# numpad_v1a.net
KiCad netlist of a schematic drawn in EAGLE
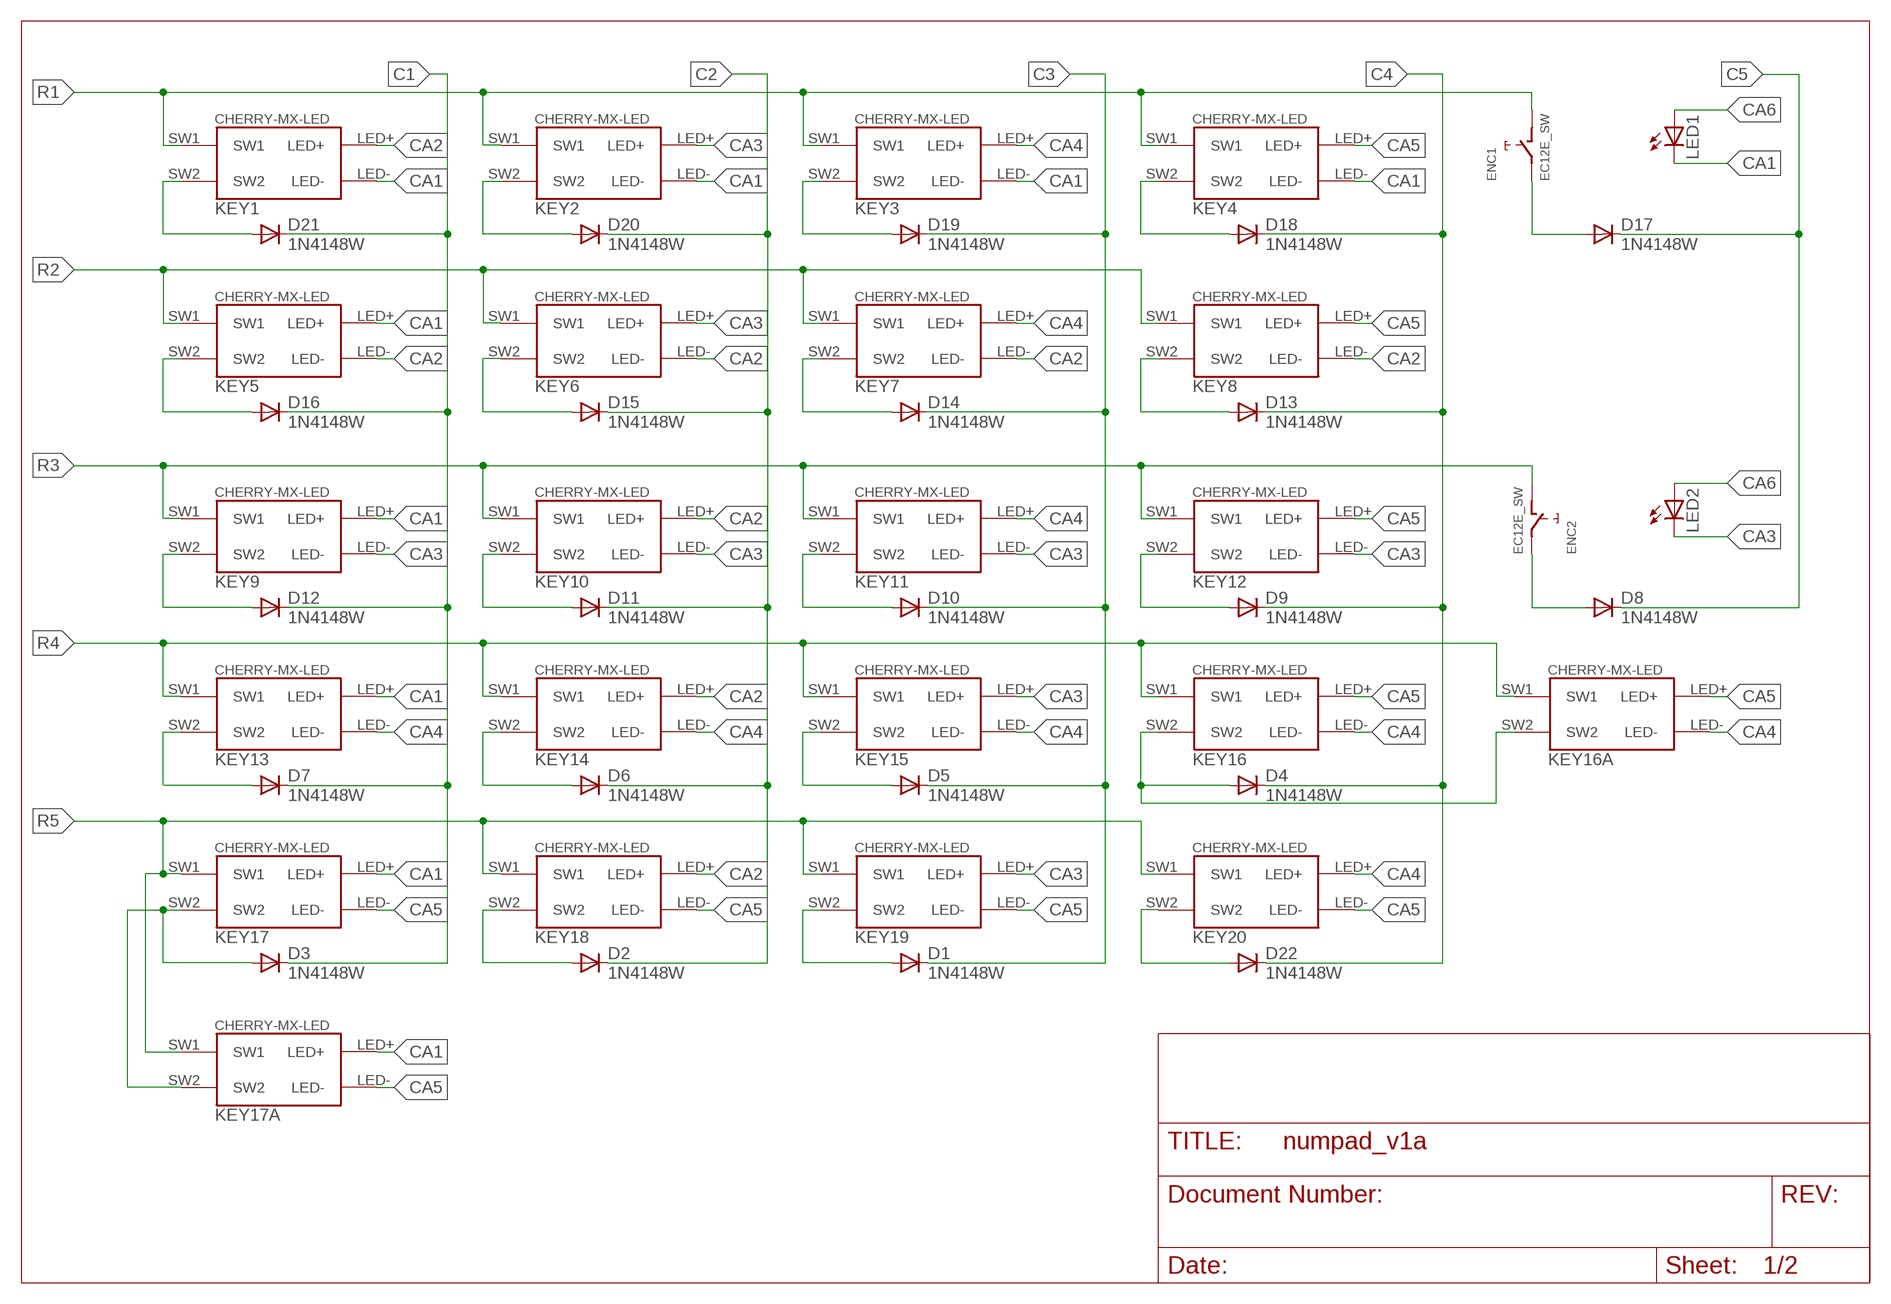
[diagram p0: schematic, sheet 1]
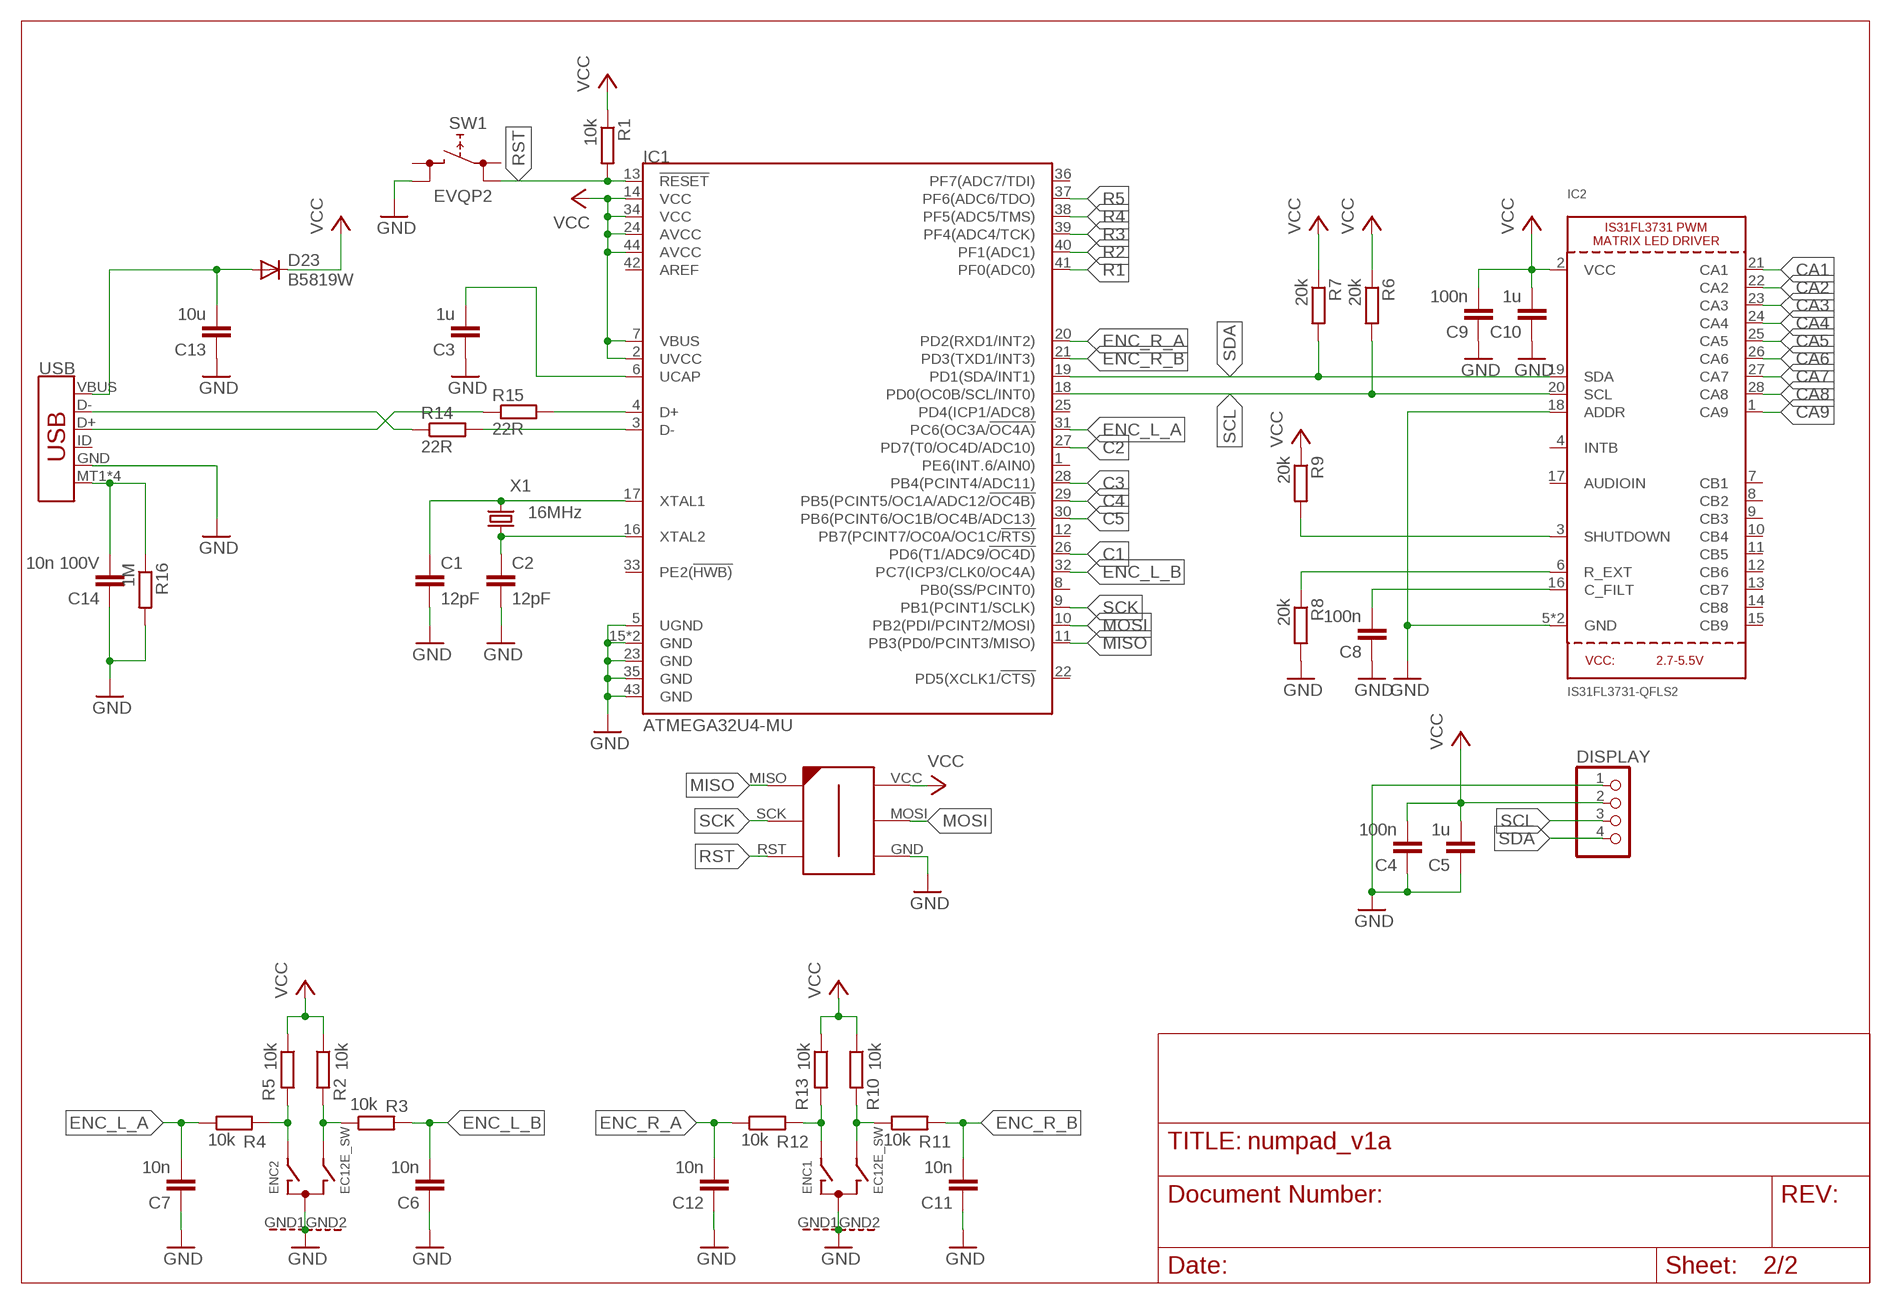
[diagram p1: schematic, sheet 2]

(export (version "E")
  (design (tool "Eeschema 10.0.6"))
  (components
    (comp (ref "D1")
      (value "1N4148W")
      (footprint "eagle-import:SOD123")
      (libsource (lib "eagle-import") (part "DIODE-SOD123"))
    )
    (comp (ref "D2")
      (value "1N4148W")
      (footprint "eagle-import:SOD123")
      (libsource (lib "eagle-import") (part "DIODE-SOD123"))
    )
    (comp (ref "D3")
      (value "1N4148W")
      (footprint "eagle-import:SOD123")
      (libsource (lib "eagle-import") (part "DIODE-SOD123"))
    )
    (comp (ref "D4")
      (value "1N4148W")
      (footprint "eagle-import:SOD123")
      (libsource (lib "eagle-import") (part "DIODE-SOD123"))
    )
    (comp (ref "D5")
      (value "1N4148W")
      (footprint "eagle-import:SOD123")
      (libsource (lib "eagle-import") (part "DIODE-SOD123"))
    )
    (comp (ref "D6")
      (value "1N4148W")
      (footprint "eagle-import:SOD123")
      (libsource (lib "eagle-import") (part "DIODE-SOD123"))
    )
    (comp (ref "D7")
      (value "1N4148W")
      (footprint "eagle-import:SOD123")
      (libsource (lib "eagle-import") (part "DIODE-SOD123"))
    )
    (comp (ref "D8")
      (value "1N4148W")
      (footprint "eagle-import:SOD123")
      (libsource (lib "eagle-import") (part "DIODE-SOD123"))
    )
    (comp (ref "D9")
      (value "1N4148W")
      (footprint "eagle-import:SOD123")
      (libsource (lib "eagle-import") (part "DIODE-SOD123"))
    )
    (comp (ref "D10")
      (value "1N4148W")
      (footprint "eagle-import:SOD123")
      (libsource (lib "eagle-import") (part "DIODE-SOD123"))
    )
    (comp (ref "D11")
      (value "1N4148W")
      (footprint "eagle-import:SOD123")
      (libsource (lib "eagle-import") (part "DIODE-SOD123"))
    )
    (comp (ref "D12")
      (value "1N4148W")
      (footprint "eagle-import:SOD123")
      (libsource (lib "eagle-import") (part "DIODE-SOD123"))
    )
    (comp (ref "D13")
      (value "1N4148W")
      (footprint "eagle-import:SOD123")
      (libsource (lib "eagle-import") (part "DIODE-SOD123"))
    )
    (comp (ref "D14")
      (value "1N4148W")
      (footprint "eagle-import:SOD123")
      (libsource (lib "eagle-import") (part "DIODE-SOD123"))
    )
    (comp (ref "D15")
      (value "1N4148W")
      (footprint "eagle-import:SOD123")
      (libsource (lib "eagle-import") (part "DIODE-SOD123"))
    )
    (comp (ref "D16")
      (value "1N4148W")
      (footprint "eagle-import:SOD123")
      (libsource (lib "eagle-import") (part "DIODE-SOD123"))
    )
    (comp (ref "D17")
      (value "1N4148W")
      (footprint "eagle-import:SOD123")
      (libsource (lib "eagle-import") (part "DIODE-SOD123"))
    )
    (comp (ref "D18")
      (value "1N4148W")
      (footprint "eagle-import:SOD123")
      (libsource (lib "eagle-import") (part "DIODE-SOD123"))
    )
    (comp (ref "D19")
      (value "1N4148W")
      (footprint "eagle-import:SOD123")
      (libsource (lib "eagle-import") (part "DIODE-SOD123"))
    )
    (comp (ref "D20")
      (value "1N4148W")
      (footprint "eagle-import:SOD123")
      (libsource (lib "eagle-import") (part "DIODE-SOD123"))
    )
    (comp (ref "D21")
      (value "1N4148W")
      (footprint "eagle-import:SOD123")
      (libsource (lib "eagle-import") (part "DIODE-SOD123"))
    )
    (comp (ref "D22")
      (value "1N4148W")
      (footprint "eagle-import:SOD123")
      (libsource (lib "eagle-import") (part "DIODE-SOD123"))
    )
    (comp (ref "ENC1")
      (value "EC12E_SW")
      (footprint "eagle-import:ALPS_EC12E_SW")
      (fields (field (name "MPN") "EC12E2424407"))
      (libsource (lib "eagle-import") (part "EC12E_SW"))
    )
    (comp (ref "ENC2")
      (value "EC12E_SW")
      (footprint "eagle-import:ALPS_EC12E_SW")
      (fields (field (name "MPN") "EC12E2424407"))
      (libsource (lib "eagle-import") (part "EC12E_SW"))
    )
    (comp (ref "KEY1")
      (value "CHERRY-MX-LED")
      (footprint "eagle-import:CHERRY-MX-LED")
      (libsource (lib "eagle-import") (part "CHERRY-MX-LED"))
    )
    (comp (ref "KEY2")
      (value "CHERRY-MX-LED")
      (footprint "eagle-import:CHERRY-MX-LED")
      (libsource (lib "eagle-import") (part "CHERRY-MX-LED"))
    )
    (comp (ref "KEY3")
      (value "CHERRY-MX-LED")
      (footprint "eagle-import:CHERRY-MX-LED")
      (libsource (lib "eagle-import") (part "CHERRY-MX-LED"))
    )
    (comp (ref "KEY4")
      (value "CHERRY-MX-LED")
      (footprint "eagle-import:CHERRY-MX-LED")
      (libsource (lib "eagle-import") (part "CHERRY-MX-LED"))
    )
    (comp (ref "KEY5")
      (value "CHERRY-MX-LED")
      (footprint "eagle-import:CHERRY-MX-LED")
      (libsource (lib "eagle-import") (part "CHERRY-MX-LED"))
    )
    (comp (ref "KEY6")
      (value "CHERRY-MX-LED")
      (footprint "eagle-import:CHERRY-MX-LED")
      (libsource (lib "eagle-import") (part "CHERRY-MX-LED"))
    )
    (comp (ref "KEY7")
      (value "CHERRY-MX-LED")
      (footprint "eagle-import:CHERRY-MX-LED")
      (libsource (lib "eagle-import") (part "CHERRY-MX-LED"))
    )
    (comp (ref "KEY8")
      (value "CHERRY-MX-LED")
      (footprint "eagle-import:CHERRY-MX-LED")
      (libsource (lib "eagle-import") (part "CHERRY-MX-LED"))
    )
    (comp (ref "KEY9")
      (value "CHERRY-MX-LED")
      (footprint "eagle-import:CHERRY-MX-LED")
      (libsource (lib "eagle-import") (part "CHERRY-MX-LED"))
    )
    (comp (ref "KEY10")
      (value "CHERRY-MX-LED")
      (footprint "eagle-import:CHERRY-MX-LED")
      (libsource (lib "eagle-import") (part "CHERRY-MX-LED"))
    )
    (comp (ref "KEY11")
      (value "CHERRY-MX-LED")
      (footprint "eagle-import:CHERRY-MX-LED")
      (libsource (lib "eagle-import") (part "CHERRY-MX-LED"))
    )
    (comp (ref "KEY12")
      (value "CHERRY-MX-LED")
      (footprint "eagle-import:CHERRY-MX-LED")
      (libsource (lib "eagle-import") (part "CHERRY-MX-LED"))
    )
    (comp (ref "KEY13")
      (value "CHERRY-MX-LED")
      (footprint "eagle-import:CHERRY-MX-LED")
      (libsource (lib "eagle-import") (part "CHERRY-MX-LED"))
    )
    (comp (ref "KEY14")
      (value "CHERRY-MX-LED")
      (footprint "eagle-import:CHERRY-MX-LED")
      (libsource (lib "eagle-import") (part "CHERRY-MX-LED"))
    )
    (comp (ref "KEY15")
      (value "CHERRY-MX-LED")
      (footprint "eagle-import:CHERRY-MX-LED")
      (libsource (lib "eagle-import") (part "CHERRY-MX-LED"))
    )
    (comp (ref "KEY16")
      (value "CHERRY-MX-LED_NOHOLES")
      (footprint "eagle-import:CHERRY-MX-LED_NOHOLES")
      (libsource (lib "eagle-import") (part "CHERRY-MX-LED_NOHOLES"))
    )
    (comp (ref "KEY16A")
      (value "CHERRY-MX-LED")
      (footprint "eagle-import:CHERRY-MX-LED")
      (libsource (lib "eagle-import") (part "CHERRY-MX-LED"))
    )
    (comp (ref "KEY17")
      (value "CHERRY-MX-LED")
      (footprint "eagle-import:CHERRY-MX-LED")
      (libsource (lib "eagle-import") (part "CHERRY-MX-LED"))
    )
    (comp (ref "KEY17A")
      (value "CHERRY-MX-LED_NOHOLES")
      (footprint "eagle-import:CHERRY-MX-LED_NOHOLES")
      (libsource (lib "eagle-import") (part "CHERRY-MX-LED_NOHOLES"))
    )
    (comp (ref "KEY18")
      (value "CHERRY-MX-LED")
      (footprint "eagle-import:CHERRY-MX-LED")
      (libsource (lib "eagle-import") (part "CHERRY-MX-LED"))
    )
    (comp (ref "KEY19")
      (value "CHERRY-MX-LED")
      (footprint "eagle-import:CHERRY-MX-LED")
      (libsource (lib "eagle-import") (part "CHERRY-MX-LED"))
    )
    (comp (ref "KEY20")
      (value "CHERRY-MX-LED")
      (footprint "eagle-import:CHERRY-MX-LED")
      (libsource (lib "eagle-import") (part "CHERRY-MX-LED"))
    )
    (comp (ref "LED1")
      (value "LED3MM")
      (footprint "eagle-import:LED3MM")
      (libsource (lib "eagle-import") (part "LED3MM"))
    )
    (comp (ref "LED2")
      (value "LED3MM")
      (footprint "eagle-import:LED3MM")
      (libsource (lib "eagle-import") (part "LED3MM"))
    )
    (comp (ref "C1")
      (value "12pF")
      (footprint "eagle-import:C0603")
      (libsource (lib "eagle-import") (part "C-EUC0603"))
    )
    (comp (ref "C2")
      (value "12pF")
      (footprint "eagle-import:C0603")
      (libsource (lib "eagle-import") (part "C-EUC0603"))
    )
    (comp (ref "C3")
      (value "1u")
      (footprint "eagle-import:C0603")
      (libsource (lib "eagle-import") (part "C-EUC0603"))
    )
    (comp (ref "C4")
      (value "100n")
      (footprint "eagle-import:C0603")
      (libsource (lib "eagle-import") (part "C-EUC0603"))
    )
    (comp (ref "C5")
      (value "1u")
      (footprint "eagle-import:C0603")
      (libsource (lib "eagle-import") (part "C-EUC0603"))
    )
    (comp (ref "C6")
      (value "10n")
      (footprint "eagle-import:C0603")
      (libsource (lib "eagle-import") (part "C-EUC0603"))
    )
    (comp (ref "C7")
      (value "10n")
      (footprint "eagle-import:C0603")
      (libsource (lib "eagle-import") (part "C-EUC0603"))
    )
    (comp (ref "C8")
      (value "100n")
      (footprint "eagle-import:C0603")
      (libsource (lib "eagle-import") (part "C-EUC0603"))
    )
    (comp (ref "C9")
      (value "100n")
      (footprint "eagle-import:C0603")
      (libsource (lib "eagle-import") (part "C-EUC0603"))
    )
    (comp (ref "C10")
      (value "1u")
      (footprint "eagle-import:C0603")
      (libsource (lib "eagle-import") (part "C-EUC0603"))
    )
    (comp (ref "C11")
      (value "10n")
      (footprint "eagle-import:C0603")
      (libsource (lib "eagle-import") (part "C-EUC0603"))
    )
    (comp (ref "C12")
      (value "10n")
      (footprint "eagle-import:C0603")
      (libsource (lib "eagle-import") (part "C-EUC0603"))
    )
    (comp (ref "C13")
      (value "10u")
      (footprint "eagle-import:C0603")
      (libsource (lib "eagle-import") (part "C-EUC0603"))
    )
    (comp (ref "C14")
      (value "10n 100V")
      (footprint "eagle-import:C0603")
      (libsource (lib "eagle-import") (part "C-EUC0603"))
    )
    (comp (ref "D23")
      (value "B5819W")
      (footprint "eagle-import:SOD123")
      (libsource (lib "eagle-import") (part "DIODE-SOD123"))
    )
    (comp (ref "DISPLAY")
      (value "PINHD-1X4")
      (footprint "eagle-import:1X04")
      (libsource (lib "eagle-import") (part "PINHD-1X4"))
    )
    (comp (ref "IC1")
      (value "ATMEGA32U4-MU")
      (footprint "eagle-import:QFN44G-0.5-7X7MM")
      (fields (field (name "MF") "Microchip") (field (name "MP") "ATMEGA32U4-MUR"))
      (libsource (lib "eagle-import") (part "MCU-ATMEGA32U4-MUR(VQFN44)"))
    )
    (comp (ref "IC2")
      (value "IS31FL3731-QFLS2")
      (footprint "eagle-import:QFN28_4MM_0.4MM")
      (libsource (lib "eagle-import") (part "IS31FL3731QFN"))
    )
    (comp (ref "ISP")
      (value "AVR-ISP-6-EDGE")
      (footprint "eagle-import:6PAD_ISP")
      (libsource (lib "eagle-import") (part "AVR-ISP-6-EDGE"))
    )
    (comp (ref "R1")
      (value "10k")
      (footprint "eagle-import:R0603")
      (libsource (lib "eagle-import") (part "R-EU_R0603"))
    )
    (comp (ref "R2")
      (value "10k")
      (footprint "eagle-import:R0603")
      (libsource (lib "eagle-import") (part "R-EU_R0603"))
    )
    (comp (ref "R3")
      (value "10k")
      (footprint "eagle-import:R0603")
      (libsource (lib "eagle-import") (part "R-EU_R0603"))
    )
    (comp (ref "R4")
      (value "10k")
      (footprint "eagle-import:R0603")
      (libsource (lib "eagle-import") (part "R-EU_R0603"))
    )
    (comp (ref "R5")
      (value "10k")
      (footprint "eagle-import:R0603")
      (libsource (lib "eagle-import") (part "R-EU_R0603"))
    )
    (comp (ref "R6")
      (value "20k")
      (footprint "eagle-import:R0603")
      (libsource (lib "eagle-import") (part "R-EU_R0603"))
    )
    (comp (ref "R7")
      (value "20k")
      (footprint "eagle-import:R0603")
      (libsource (lib "eagle-import") (part "R-EU_R0603"))
    )
    (comp (ref "R8")
      (value "20k")
      (footprint "eagle-import:R0603")
      (libsource (lib "eagle-import") (part "R-EU_R0603"))
    )
    (comp (ref "R9")
      (value "20k")
      (footprint "eagle-import:R0603")
      (libsource (lib "eagle-import") (part "R-EU_R0603"))
    )
    (comp (ref "R10")
      (value "10k")
      (footprint "eagle-import:R0603")
      (libsource (lib "eagle-import") (part "R-EU_R0603"))
    )
    (comp (ref "R11")
      (value "10k")
      (footprint "eagle-import:R0603")
      (libsource (lib "eagle-import") (part "R-EU_R0603"))
    )
    (comp (ref "R12")
      (value "10k")
      (footprint "eagle-import:R0603")
      (libsource (lib "eagle-import") (part "R-EU_R0603"))
    )
    (comp (ref "R13")
      (value "10k")
      (footprint "eagle-import:R0603")
      (libsource (lib "eagle-import") (part "R-EU_R0603"))
    )
    (comp (ref "R14")
      (value "22R")
      (footprint "eagle-import:R0603")
      (libsource (lib "eagle-import") (part "R-EU_R0603"))
    )
    (comp (ref "R15")
      (value "22R")
      (footprint "eagle-import:R0603")
      (libsource (lib "eagle-import") (part "R-EU_R0603"))
    )
    (comp (ref "R16")
      (value "1M")
      (footprint "eagle-import:R0603")
      (libsource (lib "eagle-import") (part "R-EU_R0603"))
    )
    (comp (ref "SW1")
      (value "EVQP2")
      (footprint "eagle-import:EVQP2")
      (libsource (lib "eagle-import") (part "EVQP2"))
    )
    (comp (ref "USB")
      (value "USB_MICRO-B_SMT")
      (footprint "eagle-import:USB-MICROB")
      (libsource (lib "eagle-import") (part "USB_MICRO-B_SMT"))
    )
    (comp (ref "X1")
      (value "16MHz")
      (footprint "eagle-import:3.2X2.5_KX-7")
      (libsource (lib "eagle-import") (part "KX-7"))
    )
  )
  (nets
    (net (code "1") (name "C1") (class "Default")
      (node (ref "D12") (pin "C") (pinfunction "C_C") (pintype "passive"))
      (node (ref "D16") (pin "C") (pinfunction "C_C") (pintype "passive"))
      (node (ref "D21") (pin "C") (pinfunction "C_C") (pintype "passive"))
      (node (ref "D3") (pin "C") (pinfunction "C_C") (pintype "passive"))
      (node (ref "D7") (pin "C") (pinfunction "C_C") (pintype "passive"))
      (node (ref "IC1") (pin "26") (pinfunction "PD6(T1/ADC9/~{OC4D})_26") (pintype "bidirectional"))
    )
    (net (code "2") (name "C2") (class "Default")
      (node (ref "D11") (pin "C") (pinfunction "C_C") (pintype "passive"))
      (node (ref "D15") (pin "C") (pinfunction "C_C") (pintype "passive"))
      (node (ref "D2") (pin "C") (pinfunction "C_C") (pintype "passive"))
      (node (ref "D20") (pin "C") (pinfunction "C_C") (pintype "passive"))
      (node (ref "D6") (pin "C") (pinfunction "C_C") (pintype "passive"))
      (node (ref "IC1") (pin "27") (pinfunction "PD7(T0/OC4D/ADC10)_27") (pintype "bidirectional"))
    )
    (net (code "3") (name "C3") (class "Default")
      (node (ref "D1") (pin "C") (pinfunction "C_C") (pintype "passive"))
      (node (ref "D10") (pin "C") (pinfunction "C_C") (pintype "passive"))
      (node (ref "D14") (pin "C") (pinfunction "C_C") (pintype "passive"))
      (node (ref "D19") (pin "C") (pinfunction "C_C") (pintype "passive"))
      (node (ref "D5") (pin "C") (pinfunction "C_C") (pintype "passive"))
      (node (ref "IC1") (pin "28") (pinfunction "PB4(PCINT4/ADC11)_28") (pintype "bidirectional"))
    )
    (net (code "4") (name "C4") (class "Default")
      (node (ref "D13") (pin "C") (pinfunction "C_C") (pintype "passive"))
      (node (ref "D18") (pin "C") (pinfunction "C_C") (pintype "passive"))
      (node (ref "D22") (pin "C") (pinfunction "C_C") (pintype "passive"))
      (node (ref "D4") (pin "C") (pinfunction "C_C") (pintype "passive"))
      (node (ref "D9") (pin "C") (pinfunction "C_C") (pintype "passive"))
      (node (ref "IC1") (pin "29") (pinfunction "PB5(PCINT5/OC1A/ADC12/~{OC4B})_29") (pintype "bidirectional"))
    )
    (net (code "5") (name "C5") (class "Default")
      (node (ref "D17") (pin "C") (pinfunction "C_C") (pintype "passive"))
      (node (ref "D8") (pin "C") (pinfunction "C_C") (pintype "passive"))
      (node (ref "IC1") (pin "30") (pinfunction "PB6(PCINT6/OC1B/OC4B/ADC13)_30") (pintype "bidirectional"))
    )
    (net (code "6") (name "CA1") (class "Default")
      (node (ref "IC2") (pin "21") (pinfunction "CA1_21") (pintype "bidirectional"))
      (node (ref "KEY1") (pin "LED-") (pinfunction "LED-_LED-") (pintype "bidirectional"))
      (node (ref "KEY13") (pin "LED+") (pinfunction "LED+_LED+") (pintype "bidirectional"))
      (node (ref "KEY17") (pin "LED+") (pinfunction "LED+_LED+") (pintype "bidirectional"))
      (node (ref "KEY17A") (pin "LED+") (pinfunction "LED+_LED+") (pintype "bidirectional"))
      (node (ref "KEY2") (pin "LED-") (pinfunction "LED-_LED-") (pintype "bidirectional"))
      (node (ref "KEY3") (pin "LED-") (pinfunction "LED-_LED-") (pintype "bidirectional"))
      (node (ref "KEY4") (pin "LED-") (pinfunction "LED-_LED-") (pintype "bidirectional"))
      (node (ref "KEY5") (pin "LED+") (pinfunction "LED+_LED+") (pintype "bidirectional"))
      (node (ref "KEY9") (pin "LED+") (pinfunction "LED+_LED+") (pintype "bidirectional"))
      (node (ref "LED1") (pin "K") (pinfunction "C_K") (pintype "passive"))
    )
    (net (code "7") (name "CA2") (class "Default")
      (node (ref "IC2") (pin "22") (pinfunction "CA2_22") (pintype "bidirectional"))
      (node (ref "KEY1") (pin "LED+") (pinfunction "LED+_LED+") (pintype "bidirectional"))
      (node (ref "KEY10") (pin "LED+") (pinfunction "LED+_LED+") (pintype "bidirectional"))
      (node (ref "KEY14") (pin "LED+") (pinfunction "LED+_LED+") (pintype "bidirectional"))
      (node (ref "KEY18") (pin "LED+") (pinfunction "LED+_LED+") (pintype "bidirectional"))
      (node (ref "KEY5") (pin "LED-") (pinfunction "LED-_LED-") (pintype "bidirectional"))
      (node (ref "KEY6") (pin "LED-") (pinfunction "LED-_LED-") (pintype "bidirectional"))
      (node (ref "KEY7") (pin "LED-") (pinfunction "LED-_LED-") (pintype "bidirectional"))
      (node (ref "KEY8") (pin "LED-") (pinfunction "LED-_LED-") (pintype "bidirectional"))
    )
    (net (code "8") (name "CA3") (class "Default")
      (node (ref "IC2") (pin "23") (pinfunction "CA3_23") (pintype "bidirectional"))
      (node (ref "KEY10") (pin "LED-") (pinfunction "LED-_LED-") (pintype "bidirectional"))
      (node (ref "KEY11") (pin "LED-") (pinfunction "LED-_LED-") (pintype "bidirectional"))
      (node (ref "KEY12") (pin "LED-") (pinfunction "LED-_LED-") (pintype "bidirectional"))
      (node (ref "KEY15") (pin "LED+") (pinfunction "LED+_LED+") (pintype "bidirectional"))
      (node (ref "KEY19") (pin "LED+") (pinfunction "LED+_LED+") (pintype "bidirectional"))
      (node (ref "KEY2") (pin "LED+") (pinfunction "LED+_LED+") (pintype "bidirectional"))
      (node (ref "KEY6") (pin "LED+") (pinfunction "LED+_LED+") (pintype "bidirectional"))
      (node (ref "KEY9") (pin "LED-") (pinfunction "LED-_LED-") (pintype "bidirectional"))
      (node (ref "LED2") (pin "K") (pinfunction "C_K") (pintype "passive"))
    )
    (net (code "9") (name "CA4") (class "Default")
      (node (ref "IC2") (pin "24") (pinfunction "CA4_24") (pintype "bidirectional"))
      (node (ref "KEY11") (pin "LED+") (pinfunction "LED+_LED+") (pintype "bidirectional"))
      (node (ref "KEY13") (pin "LED-") (pinfunction "LED-_LED-") (pintype "bidirectional"))
      (node (ref "KEY14") (pin "LED-") (pinfunction "LED-_LED-") (pintype "bidirectional"))
      (node (ref "KEY15") (pin "LED-") (pinfunction "LED-_LED-") (pintype "bidirectional"))
      (node (ref "KEY16") (pin "LED-") (pinfunction "LED-_LED-") (pintype "bidirectional"))
      (node (ref "KEY16A") (pin "LED-") (pinfunction "LED-_LED-") (pintype "bidirectional"))
      (node (ref "KEY20") (pin "LED+") (pinfunction "LED+_LED+") (pintype "bidirectional"))
      (node (ref "KEY3") (pin "LED+") (pinfunction "LED+_LED+") (pintype "bidirectional"))
      (node (ref "KEY7") (pin "LED+") (pinfunction "LED+_LED+") (pintype "bidirectional"))
    )
    (net (code "10") (name "CA5") (class "Default")
      (node (ref "IC2") (pin "25") (pinfunction "CA5_25") (pintype "bidirectional"))
      (node (ref "KEY12") (pin "LED+") (pinfunction "LED+_LED+") (pintype "bidirectional"))
      (node (ref "KEY16") (pin "LED+") (pinfunction "LED+_LED+") (pintype "bidirectional"))
      (node (ref "KEY16A") (pin "LED+") (pinfunction "LED+_LED+") (pintype "bidirectional"))
      (node (ref "KEY17") (pin "LED-") (pinfunction "LED-_LED-") (pintype "bidirectional"))
      (node (ref "KEY17A") (pin "LED-") (pinfunction "LED-_LED-") (pintype "bidirectional"))
      (node (ref "KEY18") (pin "LED-") (pinfunction "LED-_LED-") (pintype "bidirectional"))
      (node (ref "KEY19") (pin "LED-") (pinfunction "LED-_LED-") (pintype "bidirectional"))
      (node (ref "KEY20") (pin "LED-") (pinfunction "LED-_LED-") (pintype "bidirectional"))
      (node (ref "KEY4") (pin "LED+") (pinfunction "LED+_LED+") (pintype "bidirectional"))
      (node (ref "KEY8") (pin "LED+") (pinfunction "LED+_LED+") (pintype "bidirectional"))
    )
    (net (code "11") (name "CA6") (class "Default")
      (node (ref "IC2") (pin "26") (pinfunction "CA6_26") (pintype "bidirectional"))
      (node (ref "LED1") (pin "A") (pinfunction "A_A") (pintype "passive"))
      (node (ref "LED2") (pin "A") (pinfunction "A_A") (pintype "passive"))
    )
    (net (code "12") (name "CA7") (class "Default")
      (node (ref "IC2") (pin "27") (pinfunction "CA7_27") (pintype "bidirectional"))
    )
    (net (code "13") (name "CA8") (class "Default")
      (node (ref "IC2") (pin "28") (pinfunction "CA8_28") (pintype "bidirectional"))
    )
    (net (code "14") (name "CA9") (class "Default")
      (node (ref "IC2") (pin "1") (pinfunction "CA9_1") (pintype "bidirectional"))
    )
    (net (code "15") (name "ENC_L_A") (class "Default")
      (node (ref "C7") (pin "2") (pinfunction "2_2") (pintype "passive"))
      (node (ref "IC1") (pin "31") (pinfunction "PC6(OC3A/~{OC4A})_31") (pintype "bidirectional"))
      (node (ref "R4") (pin "1") (pinfunction "1_1") (pintype "passive"))
    )
    (net (code "16") (name "ENC_L_B") (class "Default")
      (node (ref "C6") (pin "2") (pinfunction "2_2") (pintype "passive"))
      (node (ref "IC1") (pin "32") (pinfunction "PC7(ICP3/CLK0/OC4A)_32") (pintype "bidirectional"))
      (node (ref "R3") (pin "2") (pinfunction "2_2") (pintype "passive"))
    )
    (net (code "17") (name "ENC_R_A") (class "Default")
      (node (ref "C12") (pin "2") (pinfunction "2_2") (pintype "passive"))
      (node (ref "IC1") (pin "20") (pinfunction "PD2(RXD1/INT2)_20") (pintype "bidirectional"))
      (node (ref "R12") (pin "1") (pinfunction "1_1") (pintype "passive"))
    )
    (net (code "18") (name "ENC_R_B") (class "Default")
      (node (ref "C11") (pin "2") (pinfunction "2_2") (pintype "passive"))
      (node (ref "IC1") (pin "21") (pinfunction "PD3(TXD1/INT3)_21") (pintype "bidirectional"))
      (node (ref "R11") (pin "2") (pinfunction "2_2") (pintype "passive"))
    )
    (net (code "19") (name "GND") (class "Default")
      (node (ref "C1") (pin "2") (pinfunction "2_2") (pintype "passive"))
      (node (ref "C10") (pin "1") (pinfunction "1_1") (pintype "passive"))
      (node (ref "C11") (pin "1") (pinfunction "1_1") (pintype "passive"))
      (node (ref "C12") (pin "1") (pinfunction "1_1") (pintype "passive"))
      (node (ref "C13") (pin "1") (pinfunction "1_1") (pintype "passive"))
      (node (ref "C14") (pin "1") (pinfunction "1_1") (pintype "passive"))
      (node (ref "C2") (pin "2") (pinfunction "2_2") (pintype "passive"))
      (node (ref "C3") (pin "1") (pinfunction "1_1") (pintype "passive"))
      (node (ref "C4") (pin "1") (pinfunction "1_1") (pintype "passive"))
      (node (ref "C5") (pin "1") (pinfunction "1_1") (pintype "passive"))
      (node (ref "C6") (pin "1") (pinfunction "1_1") (pintype "passive"))
      (node (ref "C7") (pin "1") (pinfunction "1_1") (pintype "passive"))
      (node (ref "C8") (pin "1") (pinfunction "1_1") (pintype "passive"))
      (node (ref "C9") (pin "1") (pinfunction "1_1") (pintype "passive"))
      (node (ref "DISPLAY") (pin "1") (pinfunction "1_1") (pintype "passive"))
      (node (ref "ENC1") (pin "C") (pinfunction "C_C") (pintype "passive"))
      (node (ref "ENC1") (pin "GND1") (pinfunction "G_GND1") (pintype "passive"))
      (node (ref "ENC1") (pin "GND2") (pinfunction "G_GND2") (pintype "passive"))
      (node (ref "ENC2") (pin "C") (pinfunction "C_C") (pintype "passive"))
      (node (ref "ENC2") (pin "GND1") (pinfunction "G_GND1") (pintype "passive"))
      (node (ref "ENC2") (pin "GND2") (pinfunction "G_GND2") (pintype "passive"))
      (node (ref "IC1") (pin "15") (pinfunction "GND_15") (pintype "bidirectional"))
      (node (ref "IC1") (pin "23") (pinfunction "GND_23") (pintype "bidirectional"))
      (node (ref "IC1") (pin "35") (pinfunction "GND_35") (pintype "bidirectional"))
      (node (ref "IC1") (pin "43") (pinfunction "GND_43") (pintype "bidirectional"))
      (node (ref "IC1") (pin "5") (pinfunction "UGND_5") (pintype "bidirectional"))
      (node (ref "IC1") (pin "TAB") (pinfunction "GND_TAB") (pintype "bidirectional"))
      (node (ref "IC2") (pin "18") (pinfunction "ADDR_18") (pintype "bidirectional"))
      (node (ref "IC2") (pin "5") (pinfunction "GND_5") (pintype "power_in"))
      (node (ref "IC2") (pin "THERMAL") (pinfunction "GND_THERMAL") (pintype "power_in"))
      (node (ref "ISP") (pin "GND") (pinfunction "P$4_GND") (pintype "bidirectional"))
      (node (ref "R16") (pin "2") (pinfunction "2_2") (pintype "passive"))
      (node (ref "R8") (pin "2") (pinfunction "2_2") (pintype "passive"))
      (node (ref "SW1") (pin "2") (pinfunction "1_2") (pintype "passive"))
      (node (ref "USB") (pin "GND") (pinfunction "GND_GND") (pintype "power_in"))
    )
    (net (code "20") (name "MISO") (class "Default")
      (node (ref "IC1") (pin "11") (pinfunction "PB3(PD0/PCINT3/MISO)_11") (pintype "bidirectional"))
      (node (ref "ISP") (pin "MISO") (pinfunction "P$1_MISO") (pintype "bidirectional"))
    )
    (net (code "21") (name "MOSI") (class "Default")
      (node (ref "IC1") (pin "10") (pinfunction "PB2(PDI/PCINT2/MOSI)_10") (pintype "bidirectional"))
      (node (ref "ISP") (pin "MOSI") (pinfunction "P$5_MOSI") (pintype "bidirectional"))
    )
    (net (code "22") (name "Net-(C13-Pad2)") (class "Default")
      (node (ref "C13") (pin "2") (pinfunction "2_2") (pintype "passive"))
      (node (ref "D23") (pin "A") (pinfunction "A_A") (pintype "passive"))
      (node (ref "USB") (pin "VBUS") (pinfunction "VBUS_VBUS") (pintype "power_in"))
    )
    (net (code "23") (name "Net-(C14-Pad2)") (class "Default")
      (node (ref "C14") (pin "2") (pinfunction "2_2") (pintype "passive"))
      (node (ref "R16") (pin "1") (pinfunction "1_1") (pintype "passive"))
      (node (ref "USB") (pin "MT1") (pinfunction "SHIELD_MT1") (pintype "bidirectional"))
      (node (ref "USB") (pin "MT2") (pinfunction "SHIELD_MT2") (pintype "bidirectional"))
      (node (ref "USB") (pin "P$1") (pinfunction "SHIELD_P$1") (pintype "bidirectional"))
      (node (ref "USB") (pin "P$2") (pinfunction "SHIELD_P$2") (pintype "bidirectional"))
    )
    (net (code "24") (name "Net-(D1-PadA)") (class "Default")
      (node (ref "D1") (pin "A") (pinfunction "A_A") (pintype "passive"))
      (node (ref "KEY19") (pin "SW2") (pinfunction "SW2_SW2") (pintype "bidirectional"))
    )
    (net (code "25") (name "Net-(D2-PadA)") (class "Default")
      (node (ref "D2") (pin "A") (pinfunction "A_A") (pintype "passive"))
      (node (ref "KEY18") (pin "SW2") (pinfunction "SW2_SW2") (pintype "bidirectional"))
    )
    (net (code "26") (name "Net-(D3-PadA)") (class "Default")
      (node (ref "D3") (pin "A") (pinfunction "A_A") (pintype "passive"))
      (node (ref "KEY17") (pin "SW2") (pinfunction "SW2_SW2") (pintype "bidirectional"))
      (node (ref "KEY17A") (pin "SW2") (pinfunction "SW2_SW2") (pintype "bidirectional"))
    )
    (net (code "27") (name "Net-(D4-PadA)") (class "Default")
      (node (ref "D4") (pin "A") (pinfunction "A_A") (pintype "passive"))
      (node (ref "KEY16") (pin "SW2") (pinfunction "SW2_SW2") (pintype "bidirectional"))
      (node (ref "KEY16A") (pin "SW2") (pinfunction "SW2_SW2") (pintype "bidirectional"))
    )
    (net (code "28") (name "Net-(D5-PadA)") (class "Default")
      (node (ref "D5") (pin "A") (pinfunction "A_A") (pintype "passive"))
      (node (ref "KEY15") (pin "SW2") (pinfunction "SW2_SW2") (pintype "bidirectional"))
    )
    (net (code "29") (name "Net-(D6-PadA)") (class "Default")
      (node (ref "D6") (pin "A") (pinfunction "A_A") (pintype "passive"))
      (node (ref "KEY14") (pin "SW2") (pinfunction "SW2_SW2") (pintype "bidirectional"))
    )
    (net (code "30") (name "Net-(D7-PadA)") (class "Default")
      (node (ref "D7") (pin "A") (pinfunction "A_A") (pintype "passive"))
      (node (ref "KEY13") (pin "SW2") (pinfunction "SW2_SW2") (pintype "bidirectional"))
    )
    (net (code "31") (name "Net-(D9-PadA)") (class "Default")
      (node (ref "D9") (pin "A") (pinfunction "A_A") (pintype "passive"))
      (node (ref "KEY12") (pin "SW2") (pinfunction "SW2_SW2") (pintype "bidirectional"))
    )
    (net (code "32") (name "Net-(D10-PadA)") (class "Default")
      (node (ref "D10") (pin "A") (pinfunction "A_A") (pintype "passive"))
      (node (ref "KEY11") (pin "SW2") (pinfunction "SW2_SW2") (pintype "bidirectional"))
    )
    (net (code "33") (name "Net-(D11-PadA)") (class "Default")
      (node (ref "D11") (pin "A") (pinfunction "A_A") (pintype "passive"))
      (node (ref "KEY10") (pin "SW2") (pinfunction "SW2_SW2") (pintype "bidirectional"))
    )
    (net (code "34") (name "Net-(D12-PadA)") (class "Default")
      (node (ref "D12") (pin "A") (pinfunction "A_A") (pintype "passive"))
      (node (ref "KEY9") (pin "SW2") (pinfunction "SW2_SW2") (pintype "bidirectional"))
    )
    (net (code "35") (name "Net-(D13-PadA)") (class "Default")
      (node (ref "D13") (pin "A") (pinfunction "A_A") (pintype "passive"))
      (node (ref "KEY8") (pin "SW2") (pinfunction "SW2_SW2") (pintype "bidirectional"))
    )
    (net (code "36") (name "Net-(D14-PadA)") (class "Default")
      (node (ref "D14") (pin "A") (pinfunction "A_A") (pintype "passive"))
      (node (ref "KEY7") (pin "SW2") (pinfunction "SW2_SW2") (pintype "bidirectional"))
    )
    (net (code "37") (name "Net-(D15-PadA)") (class "Default")
      (node (ref "D15") (pin "A") (pinfunction "A_A") (pintype "passive"))
      (node (ref "KEY6") (pin "SW2") (pinfunction "SW2_SW2") (pintype "bidirectional"))
    )
    (net (code "38") (name "Net-(D16-PadA)") (class "Default")
      (node (ref "D16") (pin "A") (pinfunction "A_A") (pintype "passive"))
      (node (ref "KEY5") (pin "SW2") (pinfunction "SW2_SW2") (pintype "bidirectional"))
    )
    (net (code "39") (name "Net-(D18-PadA)") (class "Default")
      (node (ref "D18") (pin "A") (pinfunction "A_A") (pintype "passive"))
      (node (ref "KEY4") (pin "SW2") (pinfunction "SW2_SW2") (pintype "bidirectional"))
    )
    (net (code "40") (name "Net-(D19-PadA)") (class "Default")
      (node (ref "D19") (pin "A") (pinfunction "A_A") (pintype "passive"))
      (node (ref "KEY3") (pin "SW2") (pinfunction "SW2_SW2") (pintype "bidirectional"))
    )
    (net (code "41") (name "Net-(D20-PadA)") (class "Default")
      (node (ref "D20") (pin "A") (pinfunction "A_A") (pintype "passive"))
      (node (ref "KEY2") (pin "SW2") (pinfunction "SW2_SW2") (pintype "bidirectional"))
    )
    (net (code "42") (name "Net-(D21-PadA)") (class "Default")
      (node (ref "D21") (pin "A") (pinfunction "A_A") (pintype "passive"))
      (node (ref "KEY1") (pin "SW2") (pinfunction "SW2_SW2") (pintype "bidirectional"))
    )
    (net (code "43") (name "Net-(D22-PadA)") (class "Default")
      (node (ref "D22") (pin "A") (pinfunction "A_A") (pintype "passive"))
      (node (ref "KEY20") (pin "SW2") (pinfunction "SW2_SW2") (pintype "bidirectional"))
    )
    (net (code "44") (name "Net-(ENC1-PadA)") (class "Default")
      (node (ref "ENC1") (pin "A") (pinfunction "A_A") (pintype "passive"))
      (node (ref "R12") (pin "2") (pinfunction "2_2") (pintype "passive"))
      (node (ref "R13") (pin "2") (pinfunction "2_2") (pintype "passive"))
    )
    (net (code "45") (name "Net-(ENC1-PadB)") (class "Default")
      (node (ref "ENC1") (pin "B") (pinfunction "B_B") (pintype "passive"))
      (node (ref "R10") (pin "2") (pinfunction "2_2") (pintype "passive"))
      (node (ref "R11") (pin "1") (pinfunction "1_1") (pintype "passive"))
    )
    (net (code "46") (name "Net-(ENC1B-2)") (class "Default")
      (node (ref "D17") (pin "A") (pinfunction "A_A") (pintype "passive"))
      (node (ref "ENC1") (pin "E") (pinfunction "2_E") (pintype "passive"))
    )
    (net (code "47") (name "Net-(ENC2-PadA)") (class "Default")
      (node (ref "ENC2") (pin "A") (pinfunction "A_A") (pintype "passive"))
      (node (ref "R4") (pin "2") (pinfunction "2_2") (pintype "passive"))
      (node (ref "R5") (pin "2") (pinfunction "2_2") (pintype "passive"))
    )
    (net (code "48") (name "Net-(ENC2-PadB)") (class "Default")
      (node (ref "ENC2") (pin "B") (pinfunction "B_B") (pintype "passive"))
      (node (ref "R2") (pin "2") (pinfunction "2_2") (pintype "passive"))
      (node (ref "R3") (pin "1") (pinfunction "1_1") (pintype "passive"))
    )
    (net (code "49") (name "Net-(ENC2B-2)") (class "Default")
      (node (ref "D8") (pin "A") (pinfunction "A_A") (pintype "passive"))
      (node (ref "ENC2") (pin "E") (pinfunction "2_E") (pintype "passive"))
    )
    (net (code "50") (name "Net-(IC1-D+)") (class "Default")
      (node (ref "IC1") (pin "4") (pinfunction "D+_4") (pintype "bidirectional"))
      (node (ref "R15") (pin "2") (pinfunction "2_2") (pintype "passive"))
    )
    (net (code "51") (name "Net-(IC1-D-)") (class "Default")
      (node (ref "IC1") (pin "3") (pinfunction "D-_3") (pintype "bidirectional"))
      (node (ref "R14") (pin "2") (pinfunction "2_2") (pintype "passive"))
    )
    (net (code "52") (name "Net-(IC1-UCAP)") (class "Default")
      (node (ref "C3") (pin "2") (pinfunction "2_2") (pintype "passive"))
      (node (ref "IC1") (pin "6") (pinfunction "UCAP_6") (pintype "bidirectional"))
    )
    (net (code "53") (name "Net-(IC1-XTAL1)") (class "Default")
      (node (ref "C1") (pin "1") (pinfunction "1_1") (pintype "passive"))
      (node (ref "IC1") (pin "17") (pinfunction "XTAL1_17") (pintype "bidirectional"))
      (node (ref "X1") (pin "3") (pinfunction "2_3") (pintype "passive"))
    )
    (net (code "54") (name "Net-(IC1-XTAL2)") (class "Default")
      (node (ref "C2") (pin "1") (pinfunction "1_1") (pintype "passive"))
      (node (ref "IC1") (pin "16") (pinfunction "XTAL2_16") (pintype "bidirectional"))
      (node (ref "X1") (pin "1") (pinfunction "1_1") (pintype "passive"))
    )
    (net (code "55") (name "Net-(IC2-C_FILT)") (class "Default")
      (node (ref "C8") (pin "2") (pinfunction "2_2") (pintype "passive"))
      (node (ref "IC2") (pin "16") (pinfunction "C_FILT_16") (pintype "bidirectional"))
    )
    (net (code "56") (name "Net-(IC2-R_EXT)") (class "Default")
      (node (ref "IC2") (pin "6") (pinfunction "R_EXT_6") (pintype "bidirectional"))
      (node (ref "R8") (pin "1") (pinfunction "1_1") (pintype "passive"))
    )
    (net (code "57") (name "Net-(IC2-SHUTDOWN)") (class "Default")
      (node (ref "IC2") (pin "3") (pinfunction "SHUTDOWN_3") (pintype "input"))
      (node (ref "R9") (pin "2") (pinfunction "2_2") (pintype "passive"))
    )
    (net (code "58") (name "Net-(R14-Pad1)") (class "Default")
      (node (ref "R14") (pin "1") (pinfunction "1_1") (pintype "passive"))
      (node (ref "USB") (pin "D-") (pinfunction "D-_D-") (pintype "bidirectional"))
    )
    (net (code "59") (name "Net-(R15-Pad1)") (class "Default")
      (node (ref "R15") (pin "1") (pinfunction "1_1") (pintype "passive"))
      (node (ref "USB") (pin "D+") (pinfunction "D+_D+") (pintype "bidirectional"))
    )
    (net (code "60") (name "R1") (class "Default")
      (node (ref "ENC1") (pin "D") (pinfunction "1_D") (pintype "passive"))
      (node (ref "IC1") (pin "41") (pinfunction "PF0(ADC0)_41") (pintype "bidirectional"))
      (node (ref "KEY1") (pin "SW1") (pinfunction "SW1_SW1") (pintype "bidirectional"))
      (node (ref "KEY2") (pin "SW1") (pinfunction "SW1_SW1") (pintype "bidirectional"))
      (node (ref "KEY3") (pin "SW1") (pinfunction "SW1_SW1") (pintype "bidirectional"))
      (node (ref "KEY4") (pin "SW1") (pinfunction "SW1_SW1") (pintype "bidirectional"))
    )
    (net (code "61") (name "R2") (class "Default")
      (node (ref "IC1") (pin "40") (pinfunction "PF1(ADC1)_40") (pintype "bidirectional"))
      (node (ref "KEY5") (pin "SW1") (pinfunction "SW1_SW1") (pintype "bidirectional"))
      (node (ref "KEY6") (pin "SW1") (pinfunction "SW1_SW1") (pintype "bidirectional"))
      (node (ref "KEY7") (pin "SW1") (pinfunction "SW1_SW1") (pintype "bidirectional"))
      (node (ref "KEY8") (pin "SW1") (pinfunction "SW1_SW1") (pintype "bidirectional"))
    )
    (net (code "62") (name "R3") (class "Default")
      (node (ref "ENC2") (pin "D") (pinfunction "1_D") (pintype "passive"))
      (node (ref "IC1") (pin "39") (pinfunction "PF4(ADC4/TCK)_39") (pintype "bidirectional"))
      (node (ref "KEY10") (pin "SW1") (pinfunction "SW1_SW1") (pintype "bidirectional"))
      (node (ref "KEY11") (pin "SW1") (pinfunction "SW1_SW1") (pintype "bidirectional"))
      (node (ref "KEY12") (pin "SW1") (pinfunction "SW1_SW1") (pintype "bidirectional"))
      (node (ref "KEY9") (pin "SW1") (pinfunction "SW1_SW1") (pintype "bidirectional"))
    )
    (net (code "63") (name "R4") (class "Default")
      (node (ref "IC1") (pin "38") (pinfunction "PF5(ADC5/TMS)_38") (pintype "bidirectional"))
      (node (ref "KEY13") (pin "SW1") (pinfunction "SW1_SW1") (pintype "bidirectional"))
      (node (ref "KEY14") (pin "SW1") (pinfunction "SW1_SW1") (pintype "bidirectional"))
      (node (ref "KEY15") (pin "SW1") (pinfunction "SW1_SW1") (pintype "bidirectional"))
      (node (ref "KEY16") (pin "SW1") (pinfunction "SW1_SW1") (pintype "bidirectional"))
      (node (ref "KEY16A") (pin "SW1") (pinfunction "SW1_SW1") (pintype "bidirectional"))
    )
    (net (code "64") (name "R5") (class "Default")
      (node (ref "IC1") (pin "37") (pinfunction "PF6(ADC6/TDO)_37") (pintype "bidirectional"))
      (node (ref "KEY17") (pin "SW1") (pinfunction "SW1_SW1") (pintype "bidirectional"))
      (node (ref "KEY17A") (pin "SW1") (pinfunction "SW1_SW1") (pintype "bidirectional"))
      (node (ref "KEY18") (pin "SW1") (pinfunction "SW1_SW1") (pintype "bidirectional"))
      (node (ref "KEY19") (pin "SW1") (pinfunction "SW1_SW1") (pintype "bidirectional"))
      (node (ref "KEY20") (pin "SW1") (pinfunction "SW1_SW1") (pintype "bidirectional"))
    )
    (net (code "65") (name "RST") (class "Default")
      (node (ref "IC1") (pin "13") (pinfunction "~{RESET}_13") (pintype "bidirectional"))
      (node (ref "ISP") (pin "RST") (pinfunction "P$3_RST") (pintype "bidirectional"))
      (node (ref "R1") (pin "2") (pinfunction "2_2") (pintype "passive"))
      (node (ref "SW1") (pin "3") (pinfunction "0_3") (pintype "passive"))
    )
    (net (code "66") (name "SCK") (class "Default")
      (node (ref "IC1") (pin "9") (pinfunction "PB1(PCINT1/SCLK)_9") (pintype "bidirectional"))
      (node (ref "ISP") (pin "SCK") (pinfunction "P$2_SCK") (pintype "bidirectional"))
    )
    (net (code "67") (name "SCL") (class "Default")
      (node (ref "DISPLAY") (pin "3") (pinfunction "3_3") (pintype "passive"))
      (node (ref "IC1") (pin "18") (pinfunction "PD0(OC0B/SCL/INT0)_18") (pintype "bidirectional"))
      (node (ref "IC2") (pin "20") (pinfunction "SCL_20") (pintype "bidirectional"))
      (node (ref "R6") (pin "2") (pinfunction "2_2") (pintype "passive"))
    )
    (net (code "68") (name "SDA") (class "Default")
      (node (ref "DISPLAY") (pin "4") (pinfunction "4_4") (pintype "passive"))
      (node (ref "IC1") (pin "19") (pinfunction "PD1(SDA/INT1)_19") (pintype "bidirectional"))
      (node (ref "IC2") (pin "19") (pinfunction "SDA_19") (pintype "bidirectional"))
      (node (ref "R7") (pin "2") (pinfunction "2_2") (pintype "passive"))
    )
    (net (code "69") (name "VCC") (class "Default")
      (node (ref "C10") (pin "2") (pinfunction "2_2") (pintype "passive"))
      (node (ref "C4") (pin "2") (pinfunction "2_2") (pintype "passive"))
      (node (ref "C5") (pin "2") (pinfunction "2_2") (pintype "passive"))
      (node (ref "C9") (pin "2") (pinfunction "2_2") (pintype "passive"))
      (node (ref "D23") (pin "C") (pinfunction "C_C") (pintype "passive"))
      (node (ref "DISPLAY") (pin "2") (pinfunction "2_2") (pintype "passive"))
      (node (ref "IC1") (pin "14") (pinfunction "VCC_14") (pintype "bidirectional"))
      (node (ref "IC1") (pin "2") (pinfunction "UVCC_2") (pintype "bidirectional"))
      (node (ref "IC1") (pin "24") (pinfunction "AVCC_24") (pintype "bidirectional"))
      (node (ref "IC1") (pin "34") (pinfunction "VCC_34") (pintype "bidirectional"))
      (node (ref "IC1") (pin "44") (pinfunction "AVCC_44") (pintype "bidirectional"))
      (node (ref "IC1") (pin "7") (pinfunction "VBUS_7") (pintype "bidirectional"))
      (node (ref "IC2") (pin "2") (pinfunction "VCC_2") (pintype "power_in"))
      (node (ref "ISP") (pin "VCC") (pinfunction "P$6_VCC") (pintype "bidirectional"))
      (node (ref "R1") (pin "1") (pinfunction "1_1") (pintype "passive"))
      (node (ref "R10") (pin "1") (pinfunction "1_1") (pintype "passive"))
      (node (ref "R13") (pin "1") (pinfunction "1_1") (pintype "passive"))
      (node (ref "R2") (pin "1") (pinfunction "1_1") (pintype "passive"))
      (node (ref "R5") (pin "1") (pinfunction "1_1") (pintype "passive"))
      (node (ref "R6") (pin "1") (pinfunction "1_1") (pintype "passive"))
      (node (ref "R7") (pin "1") (pinfunction "1_1") (pintype "passive"))
      (node (ref "R9") (pin "1") (pinfunction "1_1") (pintype "passive"))
    )
    (net (code "70") (name "unconnected-(IC1-AREF-Pad42)") (class "Default")
      (node (ref "IC1") (pin "42") (pinfunction "AREF_42") (pintype "bidirectional"))
    )
    (net (code "71") (name "unconnected-(IC1-PB0(SS{slash}PCINT0)-Pad8)") (class "Default")
      (node (ref "IC1") (pin "8") (pinfunction "PB0(SS/PCINT0)_8") (pintype "bidirectional"))
    )
    (net (code "72") (name "unconnected-(IC1-PB7(PCINT7{slash}OC0A{slash}OC1C{slash}~{RTS})-Pad12)") (class "Default")
      (node (ref "IC1") (pin "12") (pinfunction "PB7(PCINT7/OC0A/OC1C/~{RTS})_12") (pintype "bidirectional"))
    )
    (net (code "73") (name "unconnected-(IC1-PD4(ICP1{slash}ADC8)-Pad25)") (class "Default")
      (node (ref "IC1") (pin "25") (pinfunction "PD4(ICP1/ADC8)_25") (pintype "bidirectional"))
    )
    (net (code "74") (name "unconnected-(IC1-PD5(XCLK1{slash}~{CTS})-Pad22)") (class "Default")
      (node (ref "IC1") (pin "22") (pinfunction "PD5(XCLK1/~{CTS})_22") (pintype "bidirectional"))
    )
    (net (code "75") (name "unconnected-(IC1-PE2(~{HWB})-Pad33)") (class "Default")
      (node (ref "IC1") (pin "33") (pinfunction "PE2(~{HWB})_33") (pintype "bidirectional"))
    )
    (net (code "76") (name "unconnected-(IC1-PE6(INT.6{slash}AIN0)-Pad1)") (class "Default")
      (node (ref "IC1") (pin "1") (pinfunction "PE6(INT.6/AIN0)_1") (pintype "bidirectional"))
    )
    (net (code "77") (name "unconnected-(IC1-PF7(ADC7{slash}TDI)-Pad36)") (class "Default")
      (node (ref "IC1") (pin "36") (pinfunction "PF7(ADC7/TDI)_36") (pintype "bidirectional"))
    )
    (net (code "78") (name "unconnected-(IC2-AUDIOIN-Pad17)") (class "Default")
      (node (ref "IC2") (pin "17") (pinfunction "AUDIOIN_17") (pintype "input"))
    )
    (net (code "79") (name "unconnected-(IC2-CB1-Pad7)") (class "Default")
      (node (ref "IC2") (pin "7") (pinfunction "CB1_7") (pintype "bidirectional"))
    )
    (net (code "80") (name "unconnected-(IC2-CB2-Pad8)") (class "Default")
      (node (ref "IC2") (pin "8") (pinfunction "CB2_8") (pintype "bidirectional"))
    )
    (net (code "81") (name "unconnected-(IC2-CB3-Pad9)") (class "Default")
      (node (ref "IC2") (pin "9") (pinfunction "CB3_9") (pintype "bidirectional"))
    )
    (net (code "82") (name "unconnected-(IC2-CB4-Pad10)") (class "Default")
      (node (ref "IC2") (pin "10") (pinfunction "CB4_10") (pintype "bidirectional"))
    )
    (net (code "83") (name "unconnected-(IC2-CB5-Pad11)") (class "Default")
      (node (ref "IC2") (pin "11") (pinfunction "CB5_11") (pintype "bidirectional"))
    )
    (net (code "84") (name "unconnected-(IC2-CB6-Pad12)") (class "Default")
      (node (ref "IC2") (pin "12") (pinfunction "CB6_12") (pintype "bidirectional"))
    )
    (net (code "85") (name "unconnected-(IC2-CB7-Pad13)") (class "Default")
      (node (ref "IC2") (pin "13") (pinfunction "CB7_13") (pintype "bidirectional"))
    )
    (net (code "86") (name "unconnected-(IC2-CB8-Pad14)") (class "Default")
      (node (ref "IC2") (pin "14") (pinfunction "CB8_14") (pintype "bidirectional"))
    )
    (net (code "87") (name "unconnected-(IC2-CB9-Pad15)") (class "Default")
      (node (ref "IC2") (pin "15") (pinfunction "CB9_15") (pintype "bidirectional"))
    )
    (net (code "88") (name "unconnected-(IC2-INTB-Pad4)") (class "Default")
      (node (ref "IC2") (pin "4") (pinfunction "INTB_4") (pintype "output"))
    )
    (net (code "89") (name "unconnected-(SW1-0-Pad1)") (class "Default")
      (node (ref "SW1") (pin "1") (pinfunction "0_1") (pintype "passive"))
    )
    (net (code "90") (name "unconnected-(SW1-1-Pad4)") (class "Default")
      (node (ref "SW1") (pin "4") (pinfunction "1_4") (pintype "passive"))
    )
    (net (code "91") (name "unconnected-(USB-PadID)") (class "Default")
      (node (ref "USB") (pin "ID") (pinfunction "ID_ID") (pintype "bidirectional"))
    )
  )
)
